# OPTICS.net
KiCad netlist of a schematic drawn in Altium Designer
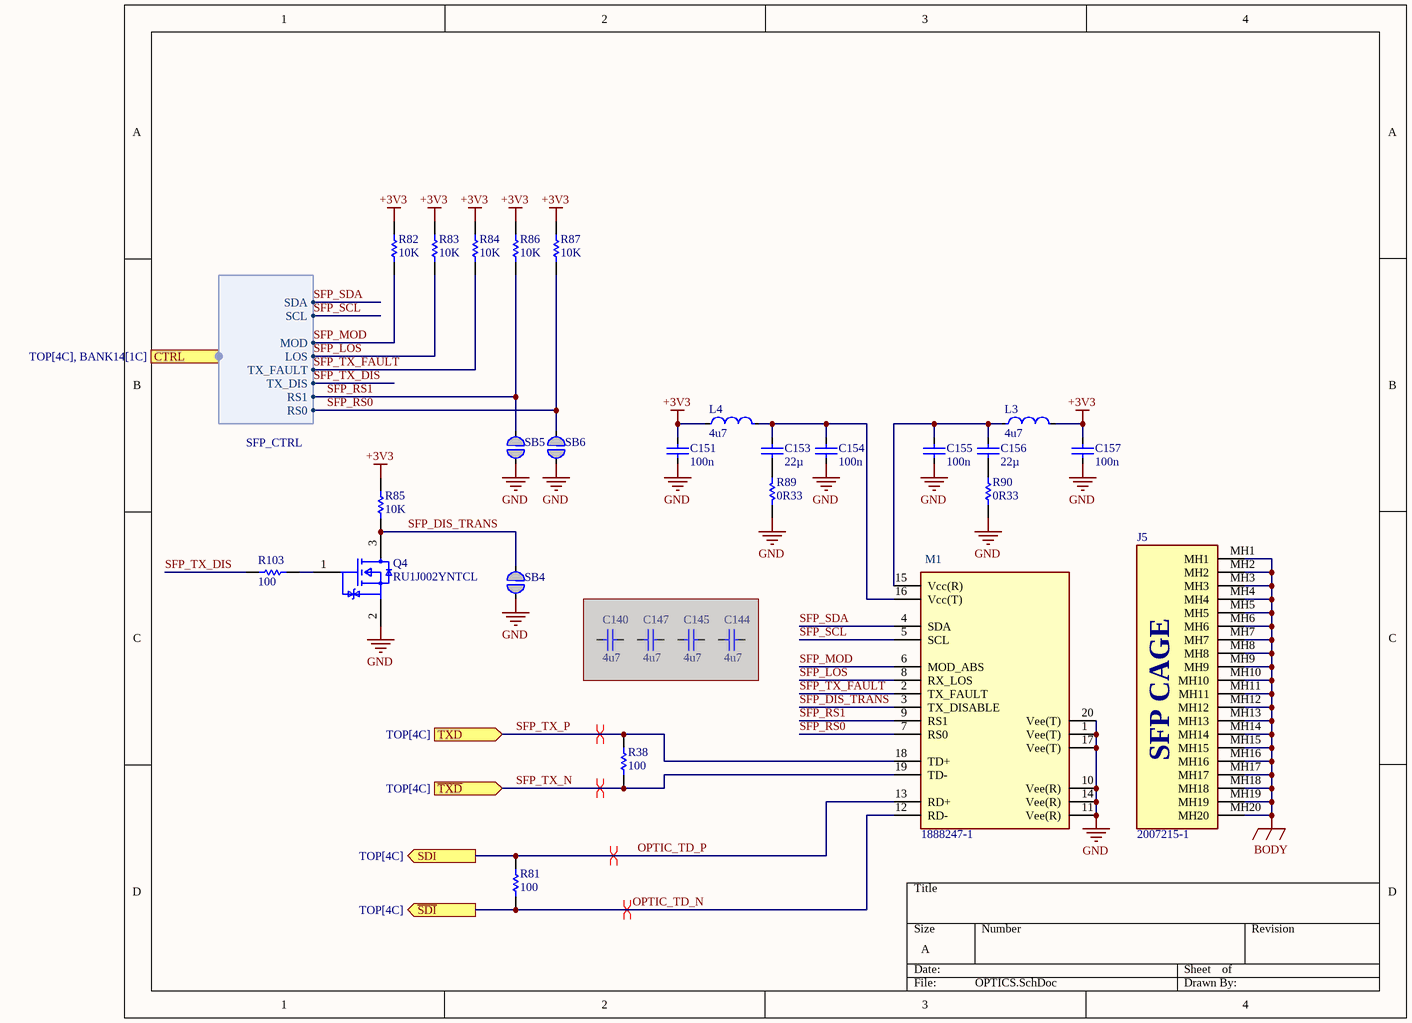
[diagram p0: OPTICS.SchDoc]

(export (version "E")
  (design (tool "Eeschema 10.0.6"))
  (components
    (comp (ref "C140")
      (value "4u7")
      (footprint "FP-C1005-050-0_20-0_10-MFG")
      (description "MLCC  4.7UF ±20 10V X5R 0402")
      (fields (field (name "TOLERANCE") "10%") (field (name "PART NUMBER") "C1005X5R1A475K050BE"))
      (libsource (lib "Schlib1") (part "C1005X5R1A475K050BE"))
    )
    (comp (ref "C144")
      (value "4u7")
      (footprint "FP-C1005-050-0_20-0_10-MFG")
      (description "MLCC  4.7UF ±20 10V X5R 0402")
      (fields (field (name "TOLERANCE") "10%") (field (name "PART NUMBER") "C1005X5R1A475K050BE"))
      (libsource (lib "Schlib1") (part "C1005X5R1A475K050BE"))
    )
    (comp (ref "C145")
      (value "4u7")
      (footprint "FP-C1005-050-0_20-0_10-MFG")
      (description "MLCC  4.7UF ±20 10V X5R 0402")
      (fields (field (name "TOLERANCE") "10%") (field (name "PART NUMBER") "C1005X5R1A475K050BE"))
      (libsource (lib "Schlib1") (part "C1005X5R1A475K050BE"))
    )
    (comp (ref "C147")
      (value "4u7")
      (footprint "FP-C1005-050-0_20-0_10-MFG")
      (description "MLCC  4.7UF ±20 10V X5R 0402")
      (fields (field (name "TOLERANCE") "10%") (field (name "PART NUMBER") "C1005X5R1A475K050BE"))
      (libsource (lib "Schlib1") (part "C1005X5R1A475K050BE"))
    )
    (comp (ref "C151")
      (value "100n")
      (footprint "FP-C1005-050-0_05-IPC_C")
      (description "MLCC 100nF ±10% 50V X7R SMD 0402")
      (fields (field (name "VOLTAGE") "50V") (field (name "TOLERANCE") "10%"))
      (libsource (lib "Schlib1") (part "C1005X7R1H104K050BB"))
    )
    (comp (ref "C153")
      (value "22µ")
      (footprint "CAPC1608X100X20LL10")
      (description "MLCC 22 uF, ±20%, 6.3 V, -55 to 85 degC, 1608 (0603 Metric), RoHS, Tape and Reel")
      (fields
        (field (name "TOLERANCE") "±20%")
        (field (name "PCN PART NUMBER") "MLCCPartNumberChange30/Nov/2012")
      )
      (libsource (lib "Schlib1") (part "C1608X5R0J226M080AC"))
    )
    (comp (ref "C154")
      (value "100n")
      (footprint "FP-C1005-050-0_05-IPC_C")
      (description "MLCC 100nF ±10% 50V X7R SMD 0402")
      (fields (field (name "VOLTAGE") "50V") (field (name "TOLERANCE") "10%"))
      (libsource (lib "Schlib1") (part "C1005X7R1H104K050BB"))
    )
    (comp (ref "C155")
      (value "100n")
      (footprint "FP-C1005-050-0_05-IPC_C")
      (description "MLCC 100nF ±10% 50V X7R SMD 0402")
      (fields (field (name "VOLTAGE") "50V") (field (name "TOLERANCE") "10%"))
      (libsource (lib "Schlib1") (part "C1005X7R1H104K050BB"))
    )
    (comp (ref "C156")
      (value "22µ")
      (footprint "CAPC1608X100X20LL10")
      (description "MLCC 22 uF, ±20%, 6.3 V, -55 to 85 degC, 1608 (0603 Metric), RoHS, Tape and Reel")
      (fields
        (field (name "TOLERANCE") "±20%")
        (field (name "PCN PART NUMBER") "MLCCPartNumberChange30/Nov/2012")
      )
      (libsource (lib "Schlib1") (part "C1608X5R0J226M080AC"))
    )
    (comp (ref "C157")
      (value "100n")
      (footprint "FP-C1005-050-0_05-IPC_C")
      (description "MLCC 100nF ±10% 50V X7R SMD 0402")
      (fields (field (name "VOLTAGE") "50V") (field (name "TOLERANCE") "10%"))
      (libsource (lib "Schlib1") (part "C1005X7R1H104K050BB"))
    )
    (comp (ref "J5")
      (value "2007215-1")
      (footprint "2007215-1")
      (libsource (lib "Schlib1") (part "2007215-1"))
    )
    (comp (ref "L3")
      (value "4u7")
      (footprint "FP-DFE252012C-MFG")
      (description "Shielded Wirewound Inductor 4.7uH 20% 1400mA 0.2Ω 1008 (2520)")
      (fields (field (name "TOLERANCE") "20%") (field (name "Comment") "DFE252012P-4R7M=P2"))
      (libsource (lib "") (part "DFE252012P-4R7M=P2_1"))
    )
    (comp (ref "L4")
      (value "4u7")
      (footprint "FP-DFE252012C-MFG")
      (description "Shielded Wirewound Inductor 4.7uH 20% 1400mA 0.2Ω 1008 (2520)")
      (fields (field (name "TOLERANCE") "20%") (field (name "Comment") "DFE252012P-4R7M=P2"))
      (libsource (lib "Schlib1") (part "DFE252012P-4R7M=P2"))
    )
    (comp (ref "M1")
      (value "1888247-1")
      (footprint "1888247-1")
      (fields (field (name "MANUFACTURER") "TE Connectivity (TE") (field (name "AUTHOR") "Parsa Malekpor"))
      (libsource (lib "Schlib1") (part "1888247-1"))
    )
    (comp (ref "Q4")
      (value "RU1J002YNTCL")
      (footprint "FP-UMT3F-MFG")
      (description "MOSFET N-CH 50V 0.2A UMT3F")
      (fields
        (field (name "MANUFACTURER") "Rohm")
        (field (name "OCTOPART") "https://octopart.com/ru1j002yntcl-rohm-47197697")
      )
      (libsource (lib "Schlib1") (part "RU1J002YNTCL"))
    )
    (comp (ref "R38")
      (value "100")
      (footprint "RESC1005X40X25LL05T10")
      (fields (field (name "PART NUMBER") "RC0402FR-07100RL") (field (name "MANUFACTURER") "Yageo / Phycomp"))
      (libsource (lib "Schlib1") (part "RC0402FR-07100RL"))
    )
    (comp (ref "R81")
      (value "100")
      (footprint "RESC1005X40X25LL05T10")
      (fields (field (name "PART NUMBER") "RC0402FR-07100RL") (field (name "MANUFACTURER") "Yageo / Phycomp"))
      (libsource (lib "Schlib1") (part "RC0402FR-07100RL"))
    )
    (comp (ref "R82")
      (value "10K")
      (footprint "RESC1005X40X25LL05T10")
      (fields (field (name "PART NUMBER") "RC0402FR-0710KL") (field (name "MANUFACTURER") "Yageo / Phycomp"))
      (libsource (lib "Schlib1") (part "RC0402FR-0710KL"))
    )
    (comp (ref "R83")
      (value "10K")
      (footprint "RESC1005X40X25LL05T10")
      (fields (field (name "PART NUMBER") "RC0402FR-0710KL") (field (name "MANUFACTURER") "Yageo / Phycomp"))
      (libsource (lib "Schlib1") (part "RC0402FR-0710KL"))
    )
    (comp (ref "R84")
      (value "10K")
      (footprint "RESC1005X40X25LL05T10")
      (fields (field (name "PART NUMBER") "RC0402FR-0710KL") (field (name "MANUFACTURER") "Yageo / Phycomp"))
      (libsource (lib "Schlib1") (part "RC0402FR-0710KL"))
    )
    (comp (ref "R85")
      (value "10K")
      (footprint "RESC1005X40X25LL05T10")
      (fields (field (name "PART NUMBER") "RC0402FR-0710KL") (field (name "MANUFACTURER") "Yageo / Phycomp"))
      (libsource (lib "Schlib1") (part "RC0402FR-0710KL"))
    )
    (comp (ref "R86")
      (value "10K")
      (footprint "RESC1005X40X25LL05T10")
      (fields (field (name "PART NUMBER") "RC0402FR-0710KL") (field (name "MANUFACTURER") "Yageo / Phycomp"))
      (libsource (lib "Schlib1") (part "RC0402FR-0710KL"))
    )
    (comp (ref "R87")
      (value "10K")
      (footprint "RESC1005X40X25LL05T10")
      (fields (field (name "PART NUMBER") "RC0402FR-0710KL") (field (name "MANUFACTURER") "Yageo / Phycomp"))
      (libsource (lib "Schlib1") (part "RC0402FR-0710KL"))
    )
    (comp (ref "R89")
      (value "0R33")
      (footprint "RESC1608X55X30LL15T15")
      (fields (field (name "PART NUMBER") "ERJ-3RQFR33V") (field (name "MANUFACTURER") "Panasonic"))
      (libsource (lib "Schlib1") (part "ERJ-3RQFR33V"))
    )
    (comp (ref "R90")
      (value "0R33")
      (footprint "RESC1608X55X30LL15T15")
      (fields (field (name "PART NUMBER") "ERJ-3RQFR33V") (field (name "MANUFACTURER") "Panasonic"))
      (libsource (lib "Schlib1") (part "ERJ-3RQFR33V"))
    )
    (comp (ref "R103")
      (value "100")
      (footprint "RESC1005X40X25LL05T10")
      (fields (field (name "PART NUMBER") "RC0402FR-07100RL") (field (name "MANUFACTURER") "Yageo / Phycomp"))
      (libsource (lib "Schlib1") (part "RC0402FR-07100RL"))
    )
    (comp (ref "SB4")
      (value "Solderbridge")
      (footprint "Solderbridge")
      (fields (field (name "MANUFACTURER") "N.A."))
      (libsource (lib "ParsaLibrary") (part "Solderbridge_1"))
    )
    (comp (ref "SB5")
      (value "Solderbridge")
      (footprint "Solderbridge")
      (fields (field (name "MANUFACTURER") "N.A."))
      (libsource (lib "ParsaLibrary") (part "Solderbridge_1"))
    )
    (comp (ref "SB6")
      (value "Solderbridge")
      (footprint "Solderbridge")
      (fields (field (name "MANUFACTURER") "N.A."))
      (libsource (lib "ParsaLibrary") (part "Solderbridge_1"))
    )
  )
  (nets
    (net (code "2") (name "+3V3") (class "Default")
      (node (ref "C151") (pin "2") (pinfunction "2_2") (pintype "passive"))
      (node (ref "C157") (pin "2") (pinfunction "2_2") (pintype "passive"))
      (node (ref "L3") (pin "2") (pinfunction "2_2") (pintype "passive"))
      (node (ref "L4") (pin "2") (pinfunction "2_2") (pintype "passive"))
      (node (ref "R82") (pin "1") (pinfunction "1_1") (pintype "passive"))
      (node (ref "R83") (pin "1") (pinfunction "1_1") (pintype "passive"))
      (node (ref "R84") (pin "1") (pinfunction "1_1") (pintype "passive"))
      (node (ref "R85") (pin "2") (pinfunction "2_2") (pintype "passive"))
      (node (ref "R86") (pin "1") (pinfunction "1_1") (pintype "passive"))
      (node (ref "R87") (pin "1") (pinfunction "1_1") (pintype "passive"))
    )
    (net (code "3") (name "/OPTIC_TD_N") (class "Default")
      (node (ref "M1") (pin "12") (pinfunction "RD-_12") (pintype "passive"))
      (node (ref "R81") (pin "2") (pinfunction "2_2") (pintype "passive"))
    )
    (net (code "4") (name "/OPTIC_TD_P") (class "Default")
      (node (ref "M1") (pin "13") (pinfunction "RD+_13") (pintype "passive"))
      (node (ref "R81") (pin "1") (pinfunction "1_1") (pintype "passive"))
    )
    (net (code "5") (name "/SFP_DIS_TRANS") (class "Default")
      (node (ref "M1") (pin "3") (pinfunction "TX_DISABLE_3") (pintype "passive"))
      (node (ref "Q4") (pin "3") (pinfunction "D_3") (pintype "passive"))
      (node (ref "R85") (pin "1") (pinfunction "1_1") (pintype "passive"))
      (node (ref "SB4") (pin "1") (pinfunction "0_1") (pintype "passive"))
    )
    (net (code "6") (name "/SFP_LOS") (class "Default")
      (node (ref "M1") (pin "8") (pinfunction "RX_LOS_8") (pintype "passive"))
      (node (ref "R83") (pin "2") (pinfunction "2_2") (pintype "passive"))
    )
    (net (code "7") (name "/SFP_MOD") (class "Default")
      (node (ref "M1") (pin "6") (pinfunction "MOD_ABS_6") (pintype "passive"))
      (node (ref "R82") (pin "2") (pinfunction "2_2") (pintype "passive"))
    )
    (net (code "8") (name "/SFP_RS0") (class "Default")
      (node (ref "M1") (pin "7") (pinfunction "RS0_7") (pintype "passive"))
      (node (ref "R87") (pin "2") (pinfunction "2_2") (pintype "passive"))
      (node (ref "SB6") (pin "1") (pinfunction "0_1") (pintype "passive"))
    )
    (net (code "9") (name "/SFP_RS1") (class "Default")
      (node (ref "M1") (pin "9") (pinfunction "RS1_9") (pintype "passive"))
      (node (ref "R86") (pin "2") (pinfunction "2_2") (pintype "passive"))
      (node (ref "SB5") (pin "1") (pinfunction "0_1") (pintype "passive"))
    )
    (net (code "10") (name "/SFP_SCL") (class "Default")
      (node (ref "M1") (pin "5") (pinfunction "SCL_5") (pintype "passive"))
    )
    (net (code "11") (name "/SFP_SDA") (class "Default")
      (node (ref "M1") (pin "4") (pinfunction "SDA_4") (pintype "passive"))
    )
    (net (code "12") (name "/SFP_TX_DIS") (class "Default")
      (node (ref "R103") (pin "1") (pinfunction "1_1") (pintype "passive"))
    )
    (net (code "13") (name "/SFP_TX_FAULT") (class "Default")
      (node (ref "M1") (pin "2") (pinfunction "TX_FAULT_2") (pintype "passive"))
      (node (ref "R84") (pin "2") (pinfunction "2_2") (pintype "passive"))
    )
    (net (code "14") (name "/SFP_TX_N") (class "Default")
      (node (ref "M1") (pin "19") (pinfunction "TD-_19") (pintype "passive"))
      (node (ref "R38") (pin "1") (pinfunction "1_1") (pintype "passive"))
    )
    (net (code "15") (name "/SFP_TX_P") (class "Default")
      (node (ref "M1") (pin "18") (pinfunction "TD+_18") (pintype "passive"))
      (node (ref "R38") (pin "2") (pinfunction "2_2") (pintype "passive"))
    )
    (net (code "17") (name "BODY") (class "Default")
      (node (ref "J5") (pin "MH1") (pinfunction "MH1_MH1") (pintype "passive"))
      (node (ref "J5") (pin "MH10") (pinfunction "MH10_MH10") (pintype "passive"))
      (node (ref "J5") (pin "MH11") (pinfunction "MH11_MH11") (pintype "passive"))
      (node (ref "J5") (pin "MH12") (pinfunction "MH12_MH12") (pintype "passive"))
      (node (ref "J5") (pin "MH13") (pinfunction "MH13_MH13") (pintype "passive"))
      (node (ref "J5") (pin "MH14") (pinfunction "MH14_MH14") (pintype "passive"))
      (node (ref "J5") (pin "MH15") (pinfunction "MH15_MH15") (pintype "passive"))
      (node (ref "J5") (pin "MH16") (pinfunction "MH16_MH16") (pintype "passive"))
      (node (ref "J5") (pin "MH17") (pinfunction "MH17_MH17") (pintype "passive"))
      (node (ref "J5") (pin "MH18") (pinfunction "MH18_MH18") (pintype "passive"))
      (node (ref "J5") (pin "MH19") (pinfunction "MH19_MH19") (pintype "passive"))
      (node (ref "J5") (pin "MH2") (pinfunction "MH2_MH2") (pintype "passive"))
      (node (ref "J5") (pin "MH20") (pinfunction "MH20_MH20") (pintype "passive"))
      (node (ref "J5") (pin "MH3") (pinfunction "MH3_MH3") (pintype "passive"))
      (node (ref "J5") (pin "MH4") (pinfunction "MH4_MH4") (pintype "passive"))
      (node (ref "J5") (pin "MH5") (pinfunction "MH5_MH5") (pintype "passive"))
      (node (ref "J5") (pin "MH6") (pinfunction "MH6_MH6") (pintype "passive"))
      (node (ref "J5") (pin "MH7") (pinfunction "MH7_MH7") (pintype "passive"))
      (node (ref "J5") (pin "MH8") (pinfunction "MH8_MH8") (pintype "passive"))
      (node (ref "J5") (pin "MH9") (pinfunction "MH9_MH9") (pintype "passive"))
    )
    (net (code "18") (name "GND") (class "Default")
      (node (ref "C151") (pin "1") (pinfunction "1_1") (pintype "passive"))
      (node (ref "C154") (pin "1") (pinfunction "1_1") (pintype "passive"))
      (node (ref "C155") (pin "1") (pinfunction "1_1") (pintype "passive"))
      (node (ref "C157") (pin "1") (pinfunction "1_1") (pintype "passive"))
      (node (ref "M1") (pin "1") (pinfunction "Vee(T)_1") (pintype "passive"))
      (node (ref "M1") (pin "10") (pinfunction "Vee(R)_10") (pintype "passive"))
      (node (ref "M1") (pin "11") (pinfunction "Vee(R)_11") (pintype "passive"))
      (node (ref "M1") (pin "14") (pinfunction "Vee(R)_14") (pintype "passive"))
      (node (ref "M1") (pin "17") (pinfunction "Vee(T)_17") (pintype "passive"))
      (node (ref "M1") (pin "20") (pinfunction "Vee(T)_20") (pintype "passive"))
      (node (ref "Q4") (pin "2") (pinfunction "S_2") (pintype "passive"))
      (node (ref "R89") (pin "2") (pinfunction "2_2") (pintype "passive"))
      (node (ref "R90") (pin "1") (pinfunction "1_1") (pintype "passive"))
      (node (ref "SB4") (pin "2") (pinfunction "1_2") (pintype "passive"))
      (node (ref "SB5") (pin "2") (pinfunction "1_2") (pintype "passive"))
      (node (ref "SB6") (pin "2") (pinfunction "1_2") (pintype "passive"))
    )
    (net (code "19") (name "Net-(C153-Pad2)") (class "Default")
      (node (ref "C153") (pin "2") (pinfunction "2_2") (pintype "passive"))
      (node (ref "R89") (pin "1") (pinfunction "1_1") (pintype "passive"))
    )
    (net (code "20") (name "Net-(C156-Pad2)") (class "Default")
      (node (ref "C156") (pin "2") (pinfunction "2_2") (pintype "passive"))
      (node (ref "R90") (pin "2") (pinfunction "2_2") (pintype "passive"))
    )
    (net (code "21") (name "Net-(M1-Vcc(R))") (class "Default")
      (node (ref "C155") (pin "2") (pinfunction "2_2") (pintype "passive"))
      (node (ref "C156") (pin "1") (pinfunction "1_1") (pintype "passive"))
      (node (ref "L3") (pin "1") (pinfunction "1_1") (pintype "passive"))
      (node (ref "M1") (pin "15") (pinfunction "Vcc(R)_15") (pintype "passive"))
    )
    (net (code "22") (name "Net-(M1-Vcc(T))") (class "Default")
      (node (ref "C153") (pin "1") (pinfunction "1_1") (pintype "passive"))
      (node (ref "C154") (pin "2") (pinfunction "2_2") (pintype "passive"))
      (node (ref "L4") (pin "1") (pinfunction "1_1") (pintype "passive"))
      (node (ref "M1") (pin "16") (pinfunction "Vcc(T)_16") (pintype "passive"))
    )
    (net (code "23") (name "Net-(Q4-G)") (class "Default")
      (node (ref "Q4") (pin "1") (pinfunction "G_1") (pintype "passive"))
      (node (ref "R103") (pin "2") (pinfunction "2_2") (pintype "passive"))
    )
    (net (code "24") (name "unconnected-(C140-Pad1)") (class "Default")
      (node (ref "C140") (pin "1") (pinfunction "1_1") (pintype "passive"))
    )
    (net (code "25") (name "unconnected-(C140-Pad2)") (class "Default")
      (node (ref "C140") (pin "2") (pinfunction "2_2") (pintype "passive"))
    )
    (net (code "26") (name "unconnected-(C144-Pad1)") (class "Default")
      (node (ref "C144") (pin "1") (pinfunction "1_1") (pintype "passive"))
    )
    (net (code "27") (name "unconnected-(C144-Pad2)") (class "Default")
      (node (ref "C144") (pin "2") (pinfunction "2_2") (pintype "passive"))
    )
    (net (code "28") (name "unconnected-(C145-Pad1)") (class "Default")
      (node (ref "C145") (pin "1") (pinfunction "1_1") (pintype "passive"))
    )
    (net (code "29") (name "unconnected-(C145-Pad2)") (class "Default")
      (node (ref "C145") (pin "2") (pinfunction "2_2") (pintype "passive"))
    )
    (net (code "30") (name "unconnected-(C147-Pad1)") (class "Default")
      (node (ref "C147") (pin "1") (pinfunction "1_1") (pintype "passive"))
    )
    (net (code "31") (name "unconnected-(C147-Pad2)") (class "Default")
      (node (ref "C147") (pin "2") (pinfunction "2_2") (pintype "passive"))
    )
  )
)
